# LM386N-stage-1-rev-1.net
KiCad netlist of a schematic drawn in EAGLE
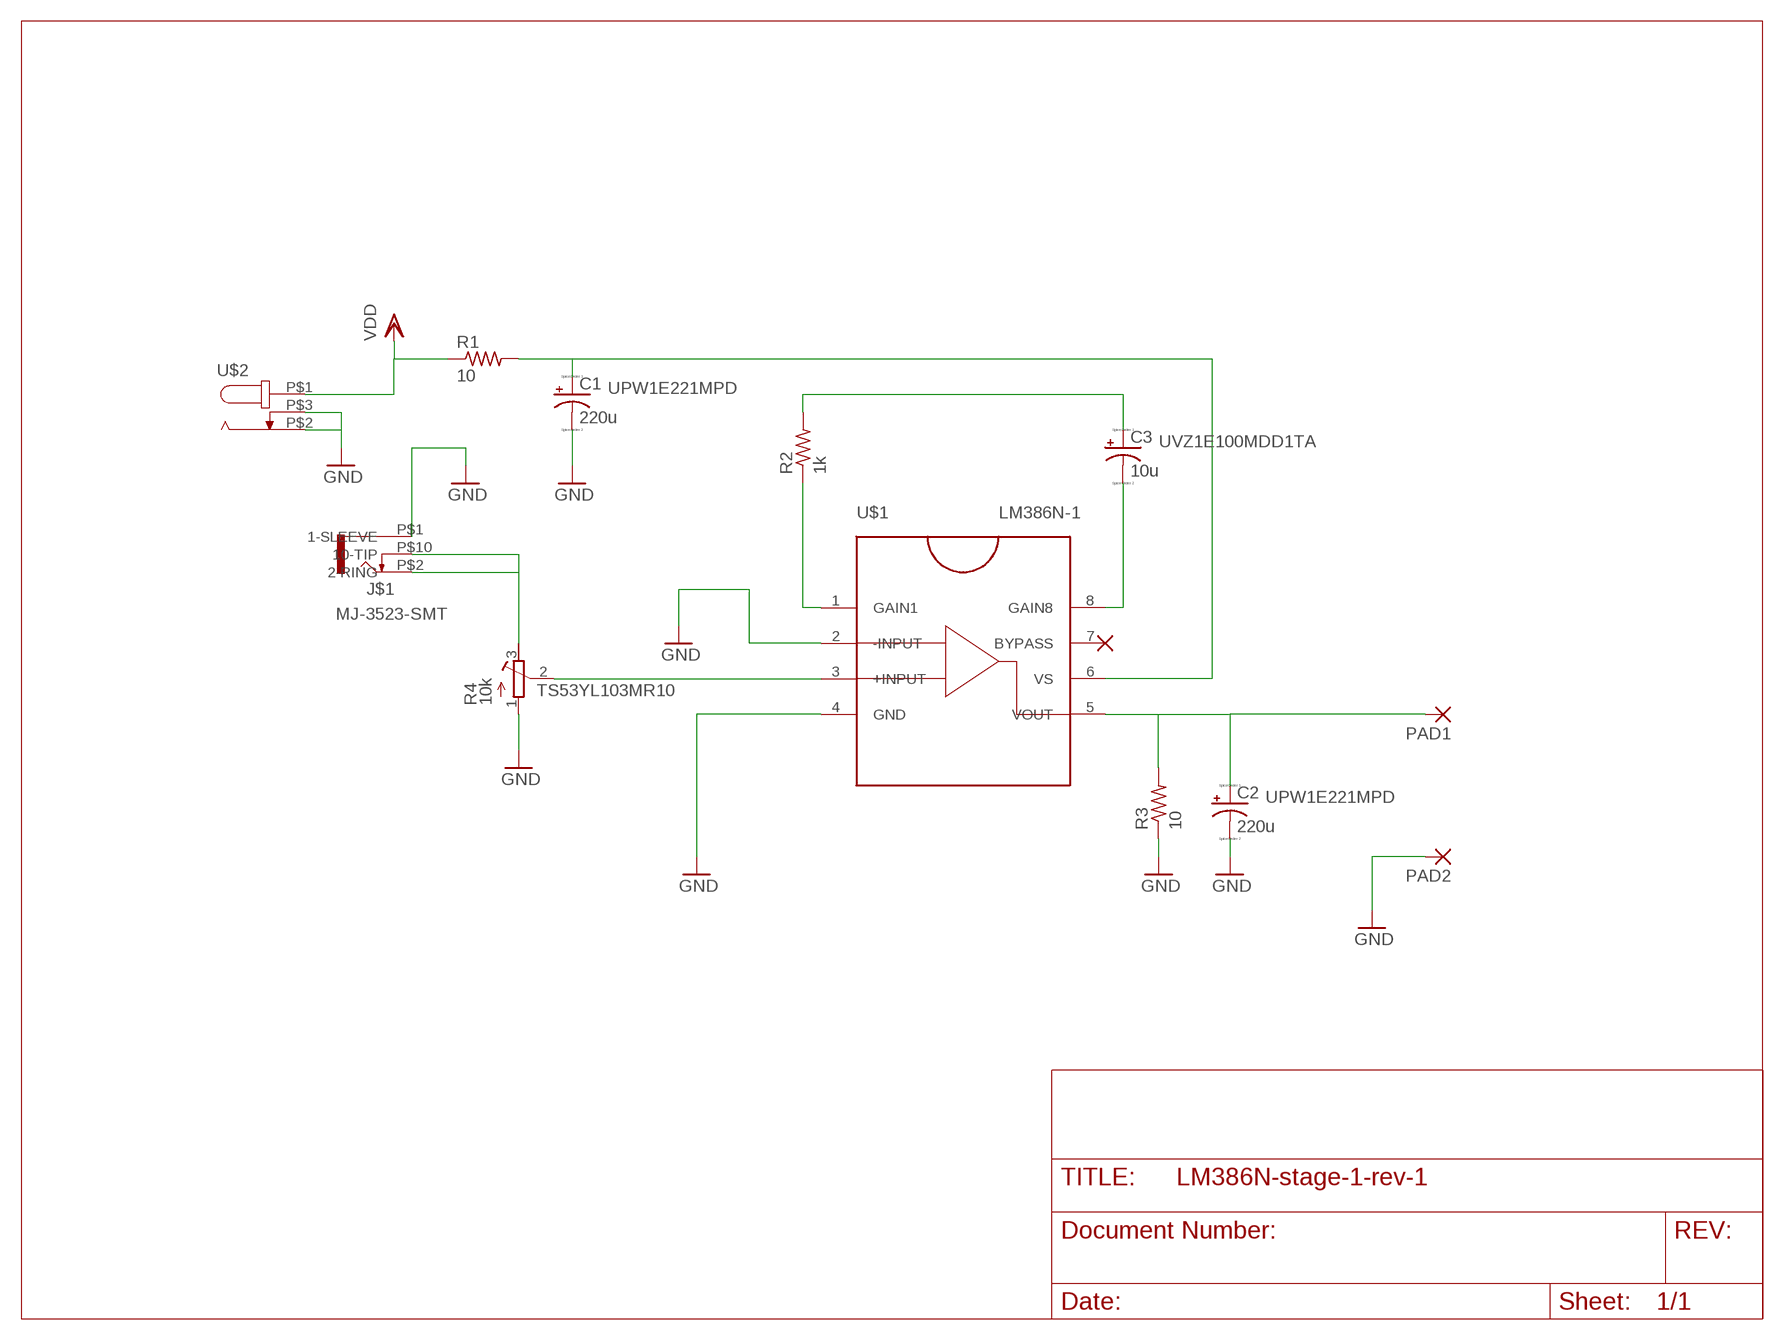
[diagram p0: schematic, sheet 1]

(export (version "E")
  (design (tool "Eeschema 10.0.6"))
  (components
    (comp (ref "C1")
      (value "220u")
      (footprint "eagle-import:E3,5-8")
      (fields (field (name "NICHICON") "UPW1E221MPD"))
      (libsource (lib "eagle-import") (part "CPOL-USE3.5-8"))
    )
    (comp (ref "C2")
      (value "220u")
      (footprint "eagle-import:E3,5-8")
      (fields (field (name "NICHICON") "UPW1E221MPD"))
      (libsource (lib "eagle-import") (part "CPOL-USE3.5-8"))
    )
    (comp (ref "C3")
      (value "10u")
      (footprint "eagle-import:E2-5")
      (fields (field (name "NICHICON") "UVZ1E100MDD1TA"))
      (libsource (lib "eagle-import") (part "CPOL-USE2-5"))
    )
    (comp (ref "J$1")
      (value "CONN-TRS-3.5MM")
      (footprint "eagle-import:MJ-3523-SMT-TR")
      (fields (field (name "CUI") "MJ-3523-SMT"))
      (libsource (lib "eagle-import") (part "CONN-TRS-3.5MM"))
    )
    (comp (ref "PAD1")
      (value "WIREPAD2,54/1,1")
      (footprint "eagle-import:2,54_1,1")
      (libsource (lib "eagle-import") (part "WIREPAD2,54/1,1"))
    )
    (comp (ref "PAD2")
      (value "WIREPAD2,54/1,1")
      (footprint "eagle-import:2,54_1,1")
      (libsource (lib "eagle-import") (part "WIREPAD2,54/1,1"))
    )
    (comp (ref "R1")
      (value "10")
      (footprint "eagle-import:0207_10")
      (libsource (lib "eagle-import") (part "R-US_0207/10"))
    )
    (comp (ref "R2")
      (value "1k")
      (footprint "eagle-import:0207_10")
      (libsource (lib "eagle-import") (part "R-US_0207/10"))
    )
    (comp (ref "R3")
      (value "10")
      (footprint "eagle-import:0207_10")
      (libsource (lib "eagle-import") (part "R-US_0207/10"))
    )
    (comp (ref "R4")
      (value "10k")
      (footprint "eagle-import:RTRIMTSM53YL")
      (fields (field (name "VISHAY") "TS53YL103MR10"))
      (libsource (lib "eagle-import") (part "R-TRIMMTSM53YL"))
    )
    (comp (ref "U$1")
      (value "LM386N-1")
      (footprint "eagle-import:DIL08")
      (libsource (lib "eagle-import") (part "LM386N-1"))
    )
    (comp (ref "U$2")
      (value "PJ-036AH-SMT-TR")
      (footprint "eagle-import:PJ-036AH-SMT-TR")
      (libsource (lib "eagle-import") (part "PJ-036AH-SMT-TR"))
    )
  )
  (nets
    (net (code "1") (name "GND") (class "Default")
      (node (ref "C1") (pin "-") (pinfunction "-_-") (pintype "passive"))
      (node (ref "C2") (pin "-") (pinfunction "-_-") (pintype "passive"))
      (node (ref "J$1") (pin "P$1") (pinfunction "1-SLEEVE_P$1") (pintype "passive"))
      (node (ref "PAD2") (pin "1") (pinfunction "P_1") (pintype "passive"))
      (node (ref "R3") (pin "1") (pinfunction "1_1") (pintype "passive"))
      (node (ref "R4") (pin "1") (pinfunction "A_1") (pintype "passive"))
      (node (ref "U$1") (pin "2") (pinfunction "-INPUT_2") (pintype "bidirectional"))
      (node (ref "U$1") (pin "4") (pinfunction "GND_4") (pintype "bidirectional"))
      (node (ref "U$2") (pin "P$2") (pinfunction "2_P$2") (pintype "passive"))
      (node (ref "U$2") (pin "P$3") (pinfunction "3_P$3") (pintype "passive"))
    )
    (net (code "2") (name "Net-(C3-Pad+)") (class "Default")
      (node (ref "C3") (pin "+") (pinfunction "+_+") (pintype "passive"))
      (node (ref "R2") (pin "2") (pinfunction "2_2") (pintype "passive"))
    )
    (net (code "3") (name "Net-(J$1-10-TIP)") (class "Default")
      (node (ref "J$1") (pin "P$10") (pinfunction "10-TIP_P$10") (pintype "passive"))
      (node (ref "J$1") (pin "P$2") (pinfunction "2-RING_P$2") (pintype "passive"))
      (node (ref "R4") (pin "3") (pinfunction "E_3") (pintype "passive"))
    )
    (net (code "4") (name "Net-(PAD1-P)") (class "Default")
      (node (ref "C2") (pin "+") (pinfunction "+_+") (pintype "passive"))
      (node (ref "PAD1") (pin "1") (pinfunction "P_1") (pintype "passive"))
      (node (ref "R3") (pin "2") (pinfunction "2_2") (pintype "passive"))
      (node (ref "U$1") (pin "5") (pinfunction "VOUT_5") (pintype "bidirectional"))
    )
    (net (code "5") (name "Net-(R4-S)") (class "Default")
      (node (ref "R4") (pin "2") (pinfunction "S_2") (pintype "passive"))
      (node (ref "U$1") (pin "3") (pinfunction "+INPUT_3") (pintype "bidirectional"))
    )
    (net (code "6") (name "Net-(U$1-GAIN1)") (class "Default")
      (node (ref "R2") (pin "1") (pinfunction "1_1") (pintype "passive"))
      (node (ref "U$1") (pin "1") (pinfunction "GAIN1_1") (pintype "bidirectional"))
    )
    (net (code "7") (name "Net-(U$1-GAIN8)") (class "Default")
      (node (ref "C3") (pin "-") (pinfunction "-_-") (pintype "passive"))
      (node (ref "U$1") (pin "8") (pinfunction "GAIN8_8") (pintype "bidirectional"))
    )
    (net (code "8") (name "Net-(U$1-VS)") (class "Default")
      (node (ref "C1") (pin "+") (pinfunction "+_+") (pintype "passive"))
      (node (ref "R1") (pin "2") (pinfunction "2_2") (pintype "passive"))
      (node (ref "U$1") (pin "6") (pinfunction "VS_6") (pintype "bidirectional"))
    )
    (net (code "9") (name "VDD") (class "Default")
      (node (ref "R1") (pin "1") (pinfunction "1_1") (pintype "passive"))
      (node (ref "U$2") (pin "P$1") (pinfunction "1_P$1") (pintype "passive"))
    )
    (net (code "10") (name "unconnected-(U$1-BYPASS-Pad7)") (class "Default")
      (node (ref "U$1") (pin "7") (pinfunction "BYPASS_7") (pintype "bidirectional"))
    )
  )
)
